# untitled.net
KiCad netlist of a schematic drawn in EAGLE
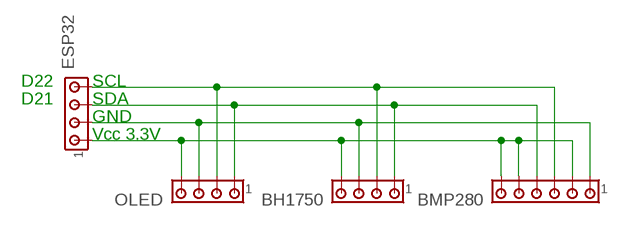
[diagram p0: schematic, sheet 1]

(export (version "E")
  (design (tool "Eeschema 10.0.6"))
  (components
    (comp (ref "BH1750")
      (value "MTA04-100")
      (footprint "eagle-import:10X04MTA")
      (libsource (lib "eagle-import") (part "MTA04-100"))
    )
    (comp (ref "BMP280")
      (value "MTA06-100")
      (footprint "eagle-import:10X06MTA")
      (libsource (lib "eagle-import") (part "MTA06-100"))
    )
    (comp (ref "ESP32")
      (value "MTA04-100")
      (footprint "eagle-import:10X04MTA")
      (libsource (lib "eagle-import") (part "MTA04-100"))
    )
    (comp (ref "OLED")
      (value "MTA04-100")
      (footprint "eagle-import:10X04MTA")
      (libsource (lib "eagle-import") (part "MTA04-100"))
    )
  )
  (nets
    (net (code "1") (name "Net-(BH1750-Pad1)") (class "Default")
      (node (ref "BH1750") (pin "1") (pinfunction "1_1") (pintype "passive"))
      (node (ref "BMP280") (pin "4") (pinfunction "4_4") (pintype "passive"))
      (node (ref "ESP32") (pin "3") (pinfunction "3_3") (pintype "passive"))
      (node (ref "OLED") (pin "1") (pinfunction "1_1") (pintype "passive"))
    )
    (net (code "2") (name "Net-(BH1750-Pad2)") (class "Default")
      (node (ref "BH1750") (pin "2") (pinfunction "2_2") (pintype "passive"))
      (node (ref "BMP280") (pin "3") (pinfunction "3_3") (pintype "passive"))
      (node (ref "ESP32") (pin "4") (pinfunction "4_4") (pintype "passive"))
      (node (ref "OLED") (pin "2") (pinfunction "2_2") (pintype "passive"))
    )
    (net (code "3") (name "Net-(BH1750-Pad3)") (class "Default")
      (node (ref "BH1750") (pin "3") (pinfunction "3_3") (pintype "passive"))
      (node (ref "BMP280") (pin "1") (pinfunction "1_1") (pintype "passive"))
      (node (ref "ESP32") (pin "2") (pinfunction "2_2") (pintype "passive"))
      (node (ref "OLED") (pin "3") (pinfunction "3_3") (pintype "passive"))
    )
    (net (code "4") (name "Net-(BH1750-Pad4)") (class "Default")
      (node (ref "BH1750") (pin "4") (pinfunction "4_4") (pintype "passive"))
      (node (ref "BMP280") (pin "2") (pinfunction "2_2") (pintype "passive"))
      (node (ref "BMP280") (pin "5") (pinfunction "5_5") (pintype "passive"))
      (node (ref "BMP280") (pin "6") (pinfunction "6_6") (pintype "passive"))
      (node (ref "ESP32") (pin "1") (pinfunction "1_1") (pintype "passive"))
      (node (ref "OLED") (pin "4") (pinfunction "4_4") (pintype "passive"))
    )
  )
)
